# M507A.net
KiCad netlist of a schematic drawn in EAGLE
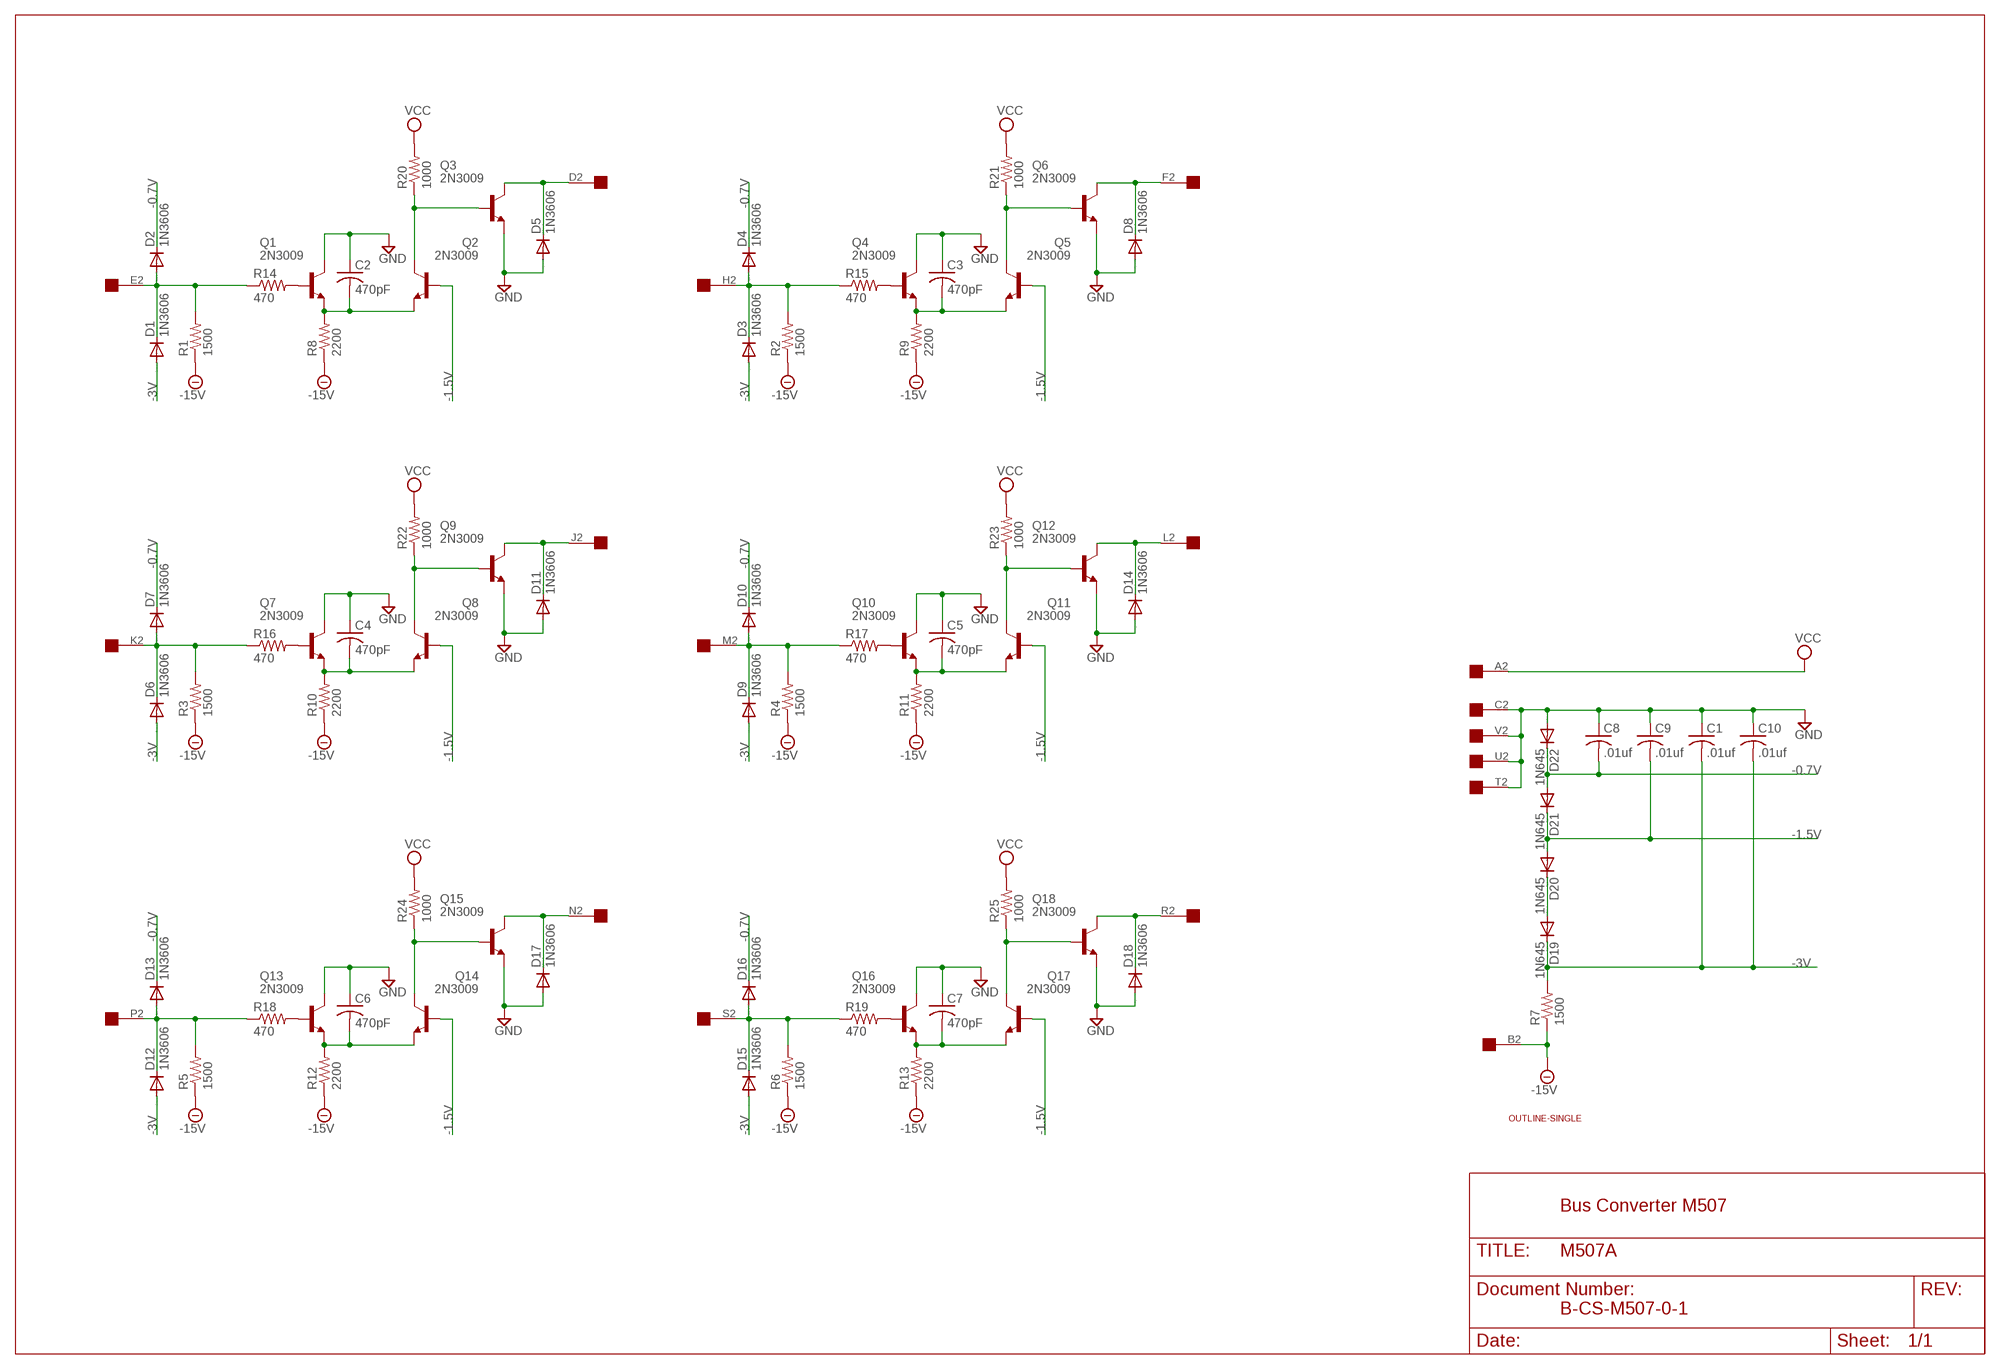
[diagram p0: schematic, sheet 1]

(export (version "E")
  (design (tool "Eeschema 10.0.6"))
  (components
    (comp (ref "C1")
      (value ".01uf")
      (footprint "eagle-import:C050-025X075")
      (libsource (lib "eagle-import") (part "C-US050-025X075"))
    )
    (comp (ref "C2")
      (value "470pF")
      (footprint "eagle-import:C050-025X075")
      (libsource (lib "eagle-import") (part "C-US050-025X075"))
    )
    (comp (ref "C3")
      (value "470pF")
      (footprint "eagle-import:C050-025X075")
      (libsource (lib "eagle-import") (part "C-US050-025X075"))
    )
    (comp (ref "C4")
      (value "470pF")
      (footprint "eagle-import:C050-025X075")
      (libsource (lib "eagle-import") (part "C-US050-025X075"))
    )
    (comp (ref "C5")
      (value "470pF")
      (footprint "eagle-import:C050-025X075")
      (libsource (lib "eagle-import") (part "C-US050-025X075"))
    )
    (comp (ref "C6")
      (value "470pF")
      (footprint "eagle-import:C050-025X075")
      (libsource (lib "eagle-import") (part "C-US050-025X075"))
    )
    (comp (ref "C7")
      (value "470pF")
      (footprint "eagle-import:C050-025X075")
      (libsource (lib "eagle-import") (part "C-US050-025X075"))
    )
    (comp (ref "C8")
      (value ".01uf")
      (footprint "eagle-import:C050-025X075")
      (libsource (lib "eagle-import") (part "C-US050-025X075"))
    )
    (comp (ref "C9")
      (value ".01uf")
      (footprint "eagle-import:C050-025X075")
      (libsource (lib "eagle-import") (part "C-US050-025X075"))
    )
    (comp (ref "C10")
      (value ".01uf")
      (footprint "eagle-import:C050-025X075")
      (libsource (lib "eagle-import") (part "C-US050-025X075"))
    )
    (comp (ref "D1")
      (value "1N3606")
      (footprint "eagle-import:DO35-10")
      (libsource (lib "eagle-import") (part "1N4148DO35-10"))
    )
    (comp (ref "D2")
      (value "1N3606")
      (footprint "eagle-import:DO35-10")
      (libsource (lib "eagle-import") (part "1N4148DO35-10"))
    )
    (comp (ref "D3")
      (value "1N3606")
      (footprint "eagle-import:DO35-10")
      (libsource (lib "eagle-import") (part "1N4148DO35-10"))
    )
    (comp (ref "D4")
      (value "1N3606")
      (footprint "eagle-import:DO35-10")
      (libsource (lib "eagle-import") (part "1N4148DO35-10"))
    )
    (comp (ref "D5")
      (value "1N3606")
      (footprint "eagle-import:DO35-10")
      (libsource (lib "eagle-import") (part "1N4148DO35-10"))
    )
    (comp (ref "D6")
      (value "1N3606")
      (footprint "eagle-import:DO35-10")
      (libsource (lib "eagle-import") (part "1N4148DO35-10"))
    )
    (comp (ref "D7")
      (value "1N3606")
      (footprint "eagle-import:DO35-10")
      (libsource (lib "eagle-import") (part "1N4148DO35-10"))
    )
    (comp (ref "D8")
      (value "1N3606")
      (footprint "eagle-import:DO35-10")
      (libsource (lib "eagle-import") (part "1N4148DO35-10"))
    )
    (comp (ref "D9")
      (value "1N3606")
      (footprint "eagle-import:DO35-10")
      (libsource (lib "eagle-import") (part "1N4148DO35-10"))
    )
    (comp (ref "D10")
      (value "1N3606")
      (footprint "eagle-import:DO35-10")
      (libsource (lib "eagle-import") (part "1N4148DO35-10"))
    )
    (comp (ref "D11")
      (value "1N3606")
      (footprint "eagle-import:DO35-10")
      (libsource (lib "eagle-import") (part "1N4148DO35-10"))
    )
    (comp (ref "D12")
      (value "1N3606")
      (footprint "eagle-import:DO35-10")
      (libsource (lib "eagle-import") (part "1N4148DO35-10"))
    )
    (comp (ref "D13")
      (value "1N3606")
      (footprint "eagle-import:DO35-10")
      (libsource (lib "eagle-import") (part "1N4148DO35-10"))
    )
    (comp (ref "D14")
      (value "1N3606")
      (footprint "eagle-import:DO35-10")
      (libsource (lib "eagle-import") (part "1N4148DO35-10"))
    )
    (comp (ref "D15")
      (value "1N3606")
      (footprint "eagle-import:DO35-10")
      (libsource (lib "eagle-import") (part "1N4148DO35-10"))
    )
    (comp (ref "D16")
      (value "1N3606")
      (footprint "eagle-import:DO35-10")
      (libsource (lib "eagle-import") (part "1N4148DO35-10"))
    )
    (comp (ref "D17")
      (value "1N3606")
      (footprint "eagle-import:DO35-10")
      (libsource (lib "eagle-import") (part "1N4148DO35-10"))
    )
    (comp (ref "D18")
      (value "1N3606")
      (footprint "eagle-import:DO35-10")
      (libsource (lib "eagle-import") (part "1N4148DO35-10"))
    )
    (comp (ref "D19")
      (value "1N645")
      (footprint "eagle-import:DO35-10")
      (libsource (lib "eagle-import") (part "1N4148DO35-10"))
    )
    (comp (ref "D20")
      (value "1N645")
      (footprint "eagle-import:DO35-10")
      (libsource (lib "eagle-import") (part "1N4148DO35-10"))
    )
    (comp (ref "D21")
      (value "1N645")
      (footprint "eagle-import:DO35-10")
      (libsource (lib "eagle-import") (part "1N4148DO35-10"))
    )
    (comp (ref "D22")
      (value "1N645")
      (footprint "eagle-import:DO35-10")
      (libsource (lib "eagle-import") (part "1N4148DO35-10"))
    )
    (comp (ref "Q1")
      (value "2N3009")
      (footprint "eagle-import:TO39")
      (libsource (lib "eagle-import") (part "2N3019"))
    )
    (comp (ref "Q2")
      (value "2N3009")
      (footprint "eagle-import:TO39")
      (libsource (lib "eagle-import") (part "2N3019"))
    )
    (comp (ref "Q3")
      (value "2N3009")
      (footprint "eagle-import:TO39")
      (libsource (lib "eagle-import") (part "2N3019"))
    )
    (comp (ref "Q4")
      (value "2N3009")
      (footprint "eagle-import:TO39")
      (libsource (lib "eagle-import") (part "2N3019"))
    )
    (comp (ref "Q5")
      (value "2N3009")
      (footprint "eagle-import:TO39")
      (libsource (lib "eagle-import") (part "2N3019"))
    )
    (comp (ref "Q6")
      (value "2N3009")
      (footprint "eagle-import:TO39")
      (libsource (lib "eagle-import") (part "2N3019"))
    )
    (comp (ref "Q7")
      (value "2N3009")
      (footprint "eagle-import:TO39")
      (libsource (lib "eagle-import") (part "2N3019"))
    )
    (comp (ref "Q8")
      (value "2N3009")
      (footprint "eagle-import:TO39")
      (libsource (lib "eagle-import") (part "2N3019"))
    )
    (comp (ref "Q9")
      (value "2N3009")
      (footprint "eagle-import:TO39")
      (libsource (lib "eagle-import") (part "2N3019"))
    )
    (comp (ref "Q10")
      (value "2N3009")
      (footprint "eagle-import:TO39")
      (libsource (lib "eagle-import") (part "2N3019"))
    )
    (comp (ref "Q11")
      (value "2N3009")
      (footprint "eagle-import:TO39")
      (libsource (lib "eagle-import") (part "2N3019"))
    )
    (comp (ref "Q12")
      (value "2N3009")
      (footprint "eagle-import:TO39")
      (libsource (lib "eagle-import") (part "2N3019"))
    )
    (comp (ref "Q13")
      (value "2N3009")
      (footprint "eagle-import:TO39")
      (libsource (lib "eagle-import") (part "2N3019"))
    )
    (comp (ref "Q14")
      (value "2N3009")
      (footprint "eagle-import:TO39")
      (libsource (lib "eagle-import") (part "2N3019"))
    )
    (comp (ref "Q15")
      (value "2N3009")
      (footprint "eagle-import:TO39")
      (libsource (lib "eagle-import") (part "2N3019"))
    )
    (comp (ref "Q16")
      (value "2N3009")
      (footprint "eagle-import:TO39")
      (libsource (lib "eagle-import") (part "2N3019"))
    )
    (comp (ref "Q17")
      (value "2N3009")
      (footprint "eagle-import:TO39")
      (libsource (lib "eagle-import") (part "2N3019"))
    )
    (comp (ref "Q18")
      (value "2N3009")
      (footprint "eagle-import:TO39")
      (libsource (lib "eagle-import") (part "2N3019"))
    )
    (comp (ref "R1")
      (value "1500")
      (footprint "eagle-import:0207_10")
      (libsource (lib "eagle-import") (part "R-US_0207/10"))
    )
    (comp (ref "R2")
      (value "1500")
      (footprint "eagle-import:0207_10")
      (libsource (lib "eagle-import") (part "R-US_0207/10"))
    )
    (comp (ref "R3")
      (value "1500")
      (footprint "eagle-import:0207_10")
      (libsource (lib "eagle-import") (part "R-US_0207/10"))
    )
    (comp (ref "R4")
      (value "1500")
      (footprint "eagle-import:0207_10")
      (libsource (lib "eagle-import") (part "R-US_0207/10"))
    )
    (comp (ref "R5")
      (value "1500")
      (footprint "eagle-import:0207_10")
      (libsource (lib "eagle-import") (part "R-US_0207/10"))
    )
    (comp (ref "R6")
      (value "1500")
      (footprint "eagle-import:0207_10")
      (libsource (lib "eagle-import") (part "R-US_0207/10"))
    )
    (comp (ref "R7")
      (value "1500")
      (footprint "eagle-import:0207_10")
      (libsource (lib "eagle-import") (part "R-US_0207/10"))
    )
    (comp (ref "R8")
      (value "2200")
      (footprint "eagle-import:0207_10")
      (libsource (lib "eagle-import") (part "R-US_0207/10"))
    )
    (comp (ref "R9")
      (value "2200")
      (footprint "eagle-import:0207_10")
      (libsource (lib "eagle-import") (part "R-US_0207/10"))
    )
    (comp (ref "R10")
      (value "2200")
      (footprint "eagle-import:0207_10")
      (libsource (lib "eagle-import") (part "R-US_0207/10"))
    )
    (comp (ref "R11")
      (value "2200")
      (footprint "eagle-import:0207_10")
      (libsource (lib "eagle-import") (part "R-US_0207/10"))
    )
    (comp (ref "R12")
      (value "2200")
      (footprint "eagle-import:0207_10")
      (libsource (lib "eagle-import") (part "R-US_0207/10"))
    )
    (comp (ref "R13")
      (value "2200")
      (footprint "eagle-import:0207_10")
      (libsource (lib "eagle-import") (part "R-US_0207/10"))
    )
    (comp (ref "R14")
      (value "470")
      (footprint "eagle-import:0207_10")
      (libsource (lib "eagle-import") (part "R-US_0207/10"))
    )
    (comp (ref "R15")
      (value "470")
      (footprint "eagle-import:0207_10")
      (libsource (lib "eagle-import") (part "R-US_0207/10"))
    )
    (comp (ref "R16")
      (value "470")
      (footprint "eagle-import:0207_10")
      (libsource (lib "eagle-import") (part "R-US_0207/10"))
    )
    (comp (ref "R17")
      (value "470")
      (footprint "eagle-import:0207_10")
      (libsource (lib "eagle-import") (part "R-US_0207/10"))
    )
    (comp (ref "R18")
      (value "470")
      (footprint "eagle-import:0207_10")
      (libsource (lib "eagle-import") (part "R-US_0207/10"))
    )
    (comp (ref "R19")
      (value "470")
      (footprint "eagle-import:0207_10")
      (libsource (lib "eagle-import") (part "R-US_0207/10"))
    )
    (comp (ref "R20")
      (value "1000")
      (footprint "eagle-import:0207_10")
      (libsource (lib "eagle-import") (part "R-US_0207/10"))
    )
    (comp (ref "R21")
      (value "1000")
      (footprint "eagle-import:0207_10")
      (libsource (lib "eagle-import") (part "R-US_0207/10"))
    )
    (comp (ref "R22")
      (value "1000")
      (footprint "eagle-import:0207_10")
      (libsource (lib "eagle-import") (part "R-US_0207/10"))
    )
    (comp (ref "R23")
      (value "1000")
      (footprint "eagle-import:0207_10")
      (libsource (lib "eagle-import") (part "R-US_0207/10"))
    )
    (comp (ref "R24")
      (value "1000")
      (footprint "eagle-import:0207_10")
      (libsource (lib "eagle-import") (part "R-US_0207/10"))
    )
    (comp (ref "R25")
      (value "1000")
      (footprint "eagle-import:0207_10")
      (libsource (lib "eagle-import") (part "R-US_0207/10"))
    )
    (comp (ref "U$3")
      (value "EDGE-1")
      (footprint "eagle-import:EDGE-CON1")
      (libsource (lib "eagle-import") (part "EDGE-1"))
    )
    (comp (ref "U$4")
      (value "OUTLINE-SINGLE")
      (footprint "eagle-import:SINGLE")
      (libsource (lib "eagle-import") (part "OUTLINE-SINGLE"))
    )
  )
  (nets
    (net (code "1") (name "-15V") (class "Default")
      (node (ref "R1") (pin "1") (pinfunction "1_1") (pintype "passive"))
      (node (ref "R10") (pin "1") (pinfunction "1_1") (pintype "passive"))
      (node (ref "R11") (pin "1") (pinfunction "1_1") (pintype "passive"))
      (node (ref "R12") (pin "1") (pinfunction "1_1") (pintype "passive"))
      (node (ref "R13") (pin "1") (pinfunction "1_1") (pintype "passive"))
      (node (ref "R2") (pin "1") (pinfunction "1_1") (pintype "passive"))
      (node (ref "R3") (pin "1") (pinfunction "1_1") (pintype "passive"))
      (node (ref "R4") (pin "1") (pinfunction "1_1") (pintype "passive"))
      (node (ref "R5") (pin "1") (pinfunction "1_1") (pintype "passive"))
      (node (ref "R6") (pin "1") (pinfunction "1_1") (pintype "passive"))
      (node (ref "R7") (pin "1") (pinfunction "1_1") (pintype "passive"))
      (node (ref "R8") (pin "1") (pinfunction "1_1") (pintype "passive"))
      (node (ref "R9") (pin "1") (pinfunction "1_1") (pintype "passive"))
      (node (ref "U$3") (pin "B2") (pinfunction "1_B2") (pintype "bidirectional"))
    )
    (net (code "2") (name "/-0.7V") (class "Default")
      (node (ref "C8") (pin "2") (pinfunction "2_2") (pintype "passive"))
      (node (ref "D10") (pin "C") (pinfunction "C_C") (pintype "passive"))
      (node (ref "D13") (pin "C") (pinfunction "C_C") (pintype "passive"))
      (node (ref "D16") (pin "C") (pinfunction "C_C") (pintype "passive"))
      (node (ref "D2") (pin "C") (pinfunction "C_C") (pintype "passive"))
      (node (ref "D21") (pin "A") (pinfunction "A_A") (pintype "passive"))
      (node (ref "D22") (pin "C") (pinfunction "C_C") (pintype "passive"))
      (node (ref "D4") (pin "C") (pinfunction "C_C") (pintype "passive"))
      (node (ref "D7") (pin "C") (pinfunction "C_C") (pintype "passive"))
    )
    (net (code "3") (name "/-1.5V") (class "Default")
      (node (ref "C9") (pin "2") (pinfunction "2_2") (pintype "passive"))
      (node (ref "D20") (pin "A") (pinfunction "A_A") (pintype "passive"))
      (node (ref "D21") (pin "C") (pinfunction "C_C") (pintype "passive"))
      (node (ref "Q11") (pin "2") (pinfunction "B_2") (pintype "passive"))
      (node (ref "Q14") (pin "2") (pinfunction "B_2") (pintype "passive"))
      (node (ref "Q17") (pin "2") (pinfunction "B_2") (pintype "passive"))
      (node (ref "Q2") (pin "2") (pinfunction "B_2") (pintype "passive"))
      (node (ref "Q5") (pin "2") (pinfunction "B_2") (pintype "passive"))
      (node (ref "Q8") (pin "2") (pinfunction "B_2") (pintype "passive"))
    )
    (net (code "4") (name "/-3V") (class "Default")
      (node (ref "C1") (pin "2") (pinfunction "2_2") (pintype "passive"))
      (node (ref "C10") (pin "2") (pinfunction "2_2") (pintype "passive"))
      (node (ref "D1") (pin "A") (pinfunction "A_A") (pintype "passive"))
      (node (ref "D12") (pin "A") (pinfunction "A_A") (pintype "passive"))
      (node (ref "D15") (pin "A") (pinfunction "A_A") (pintype "passive"))
      (node (ref "D19") (pin "C") (pinfunction "C_C") (pintype "passive"))
      (node (ref "D3") (pin "A") (pinfunction "A_A") (pintype "passive"))
      (node (ref "D6") (pin "A") (pinfunction "A_A") (pintype "passive"))
      (node (ref "D9") (pin "A") (pinfunction "A_A") (pintype "passive"))
      (node (ref "R7") (pin "2") (pinfunction "2_2") (pintype "passive"))
    )
    (net (code "5") (name "GND") (class "Default")
      (node (ref "C1") (pin "1") (pinfunction "1_1") (pintype "passive"))
      (node (ref "C10") (pin "1") (pinfunction "1_1") (pintype "passive"))
      (node (ref "C2") (pin "1") (pinfunction "1_1") (pintype "passive"))
      (node (ref "C3") (pin "1") (pinfunction "1_1") (pintype "passive"))
      (node (ref "C4") (pin "1") (pinfunction "1_1") (pintype "passive"))
      (node (ref "C5") (pin "1") (pinfunction "1_1") (pintype "passive"))
      (node (ref "C6") (pin "1") (pinfunction "1_1") (pintype "passive"))
      (node (ref "C7") (pin "1") (pinfunction "1_1") (pintype "passive"))
      (node (ref "C8") (pin "1") (pinfunction "1_1") (pintype "passive"))
      (node (ref "C9") (pin "1") (pinfunction "1_1") (pintype "passive"))
      (node (ref "D11") (pin "A") (pinfunction "A_A") (pintype "passive"))
      (node (ref "D14") (pin "A") (pinfunction "A_A") (pintype "passive"))
      (node (ref "D17") (pin "A") (pinfunction "A_A") (pintype "passive"))
      (node (ref "D18") (pin "A") (pinfunction "A_A") (pintype "passive"))
      (node (ref "D22") (pin "A") (pinfunction "A_A") (pintype "passive"))
      (node (ref "D5") (pin "A") (pinfunction "A_A") (pintype "passive"))
      (node (ref "D8") (pin "A") (pinfunction "A_A") (pintype "passive"))
      (node (ref "Q1") (pin "3") (pinfunction "C_3") (pintype "passive"))
      (node (ref "Q10") (pin "3") (pinfunction "C_3") (pintype "passive"))
      (node (ref "Q12") (pin "1") (pinfunction "E_1") (pintype "passive"))
      (node (ref "Q13") (pin "3") (pinfunction "C_3") (pintype "passive"))
      (node (ref "Q15") (pin "1") (pinfunction "E_1") (pintype "passive"))
      (node (ref "Q16") (pin "3") (pinfunction "C_3") (pintype "passive"))
      (node (ref "Q18") (pin "1") (pinfunction "E_1") (pintype "passive"))
      (node (ref "Q3") (pin "1") (pinfunction "E_1") (pintype "passive"))
      (node (ref "Q4") (pin "3") (pinfunction "C_3") (pintype "passive"))
      (node (ref "Q6") (pin "1") (pinfunction "E_1") (pintype "passive"))
      (node (ref "Q7") (pin "3") (pinfunction "C_3") (pintype "passive"))
      (node (ref "Q9") (pin "1") (pinfunction "E_1") (pintype "passive"))
      (node (ref "U$3") (pin "C2") (pinfunction "1_C2") (pintype "bidirectional"))
      (node (ref "U$3") (pin "T2") (pinfunction "1_T2") (pintype "bidirectional"))
      (node (ref "U$3") (pin "U2") (pinfunction "1_U2") (pintype "bidirectional"))
      (node (ref "U$3") (pin "V2") (pinfunction "1_V2") (pintype "bidirectional"))
    )
    (net (code "6") (name "Net-(D19-PadA)") (class "Default")
      (node (ref "D19") (pin "A") (pinfunction "A_A") (pintype "passive"))
      (node (ref "D20") (pin "C") (pinfunction "C_C") (pintype "passive"))
    )
    (net (code "7") (name "Net-(Q1-B)") (class "Default")
      (node (ref "Q1") (pin "2") (pinfunction "B_2") (pintype "passive"))
      (node (ref "R14") (pin "2") (pinfunction "2_2") (pintype "passive"))
    )
    (net (code "8") (name "Net-(Q1-E)") (class "Default")
      (node (ref "C2") (pin "2") (pinfunction "2_2") (pintype "passive"))
      (node (ref "Q1") (pin "1") (pinfunction "E_1") (pintype "passive"))
      (node (ref "Q2") (pin "1") (pinfunction "E_1") (pintype "passive"))
      (node (ref "R8") (pin "2") (pinfunction "2_2") (pintype "passive"))
    )
    (net (code "9") (name "Net-(Q2-C)") (class "Default")
      (node (ref "Q2") (pin "3") (pinfunction "C_3") (pintype "passive"))
      (node (ref "Q3") (pin "2") (pinfunction "B_2") (pintype "passive"))
      (node (ref "R20") (pin "1") (pinfunction "1_1") (pintype "passive"))
    )
    (net (code "10") (name "Net-(Q3-C)") (class "Default")
      (node (ref "D5") (pin "C") (pinfunction "C_C") (pintype "passive"))
      (node (ref "Q3") (pin "3") (pinfunction "C_3") (pintype "passive"))
      (node (ref "U$3") (pin "D2") (pinfunction "1_D2") (pintype "bidirectional"))
    )
    (net (code "11") (name "Net-(Q4-B)") (class "Default")
      (node (ref "Q4") (pin "2") (pinfunction "B_2") (pintype "passive"))
      (node (ref "R15") (pin "2") (pinfunction "2_2") (pintype "passive"))
    )
    (net (code "12") (name "Net-(Q4-E)") (class "Default")
      (node (ref "C3") (pin "2") (pinfunction "2_2") (pintype "passive"))
      (node (ref "Q4") (pin "1") (pinfunction "E_1") (pintype "passive"))
      (node (ref "Q5") (pin "1") (pinfunction "E_1") (pintype "passive"))
      (node (ref "R9") (pin "2") (pinfunction "2_2") (pintype "passive"))
    )
    (net (code "13") (name "Net-(Q5-C)") (class "Default")
      (node (ref "Q5") (pin "3") (pinfunction "C_3") (pintype "passive"))
      (node (ref "Q6") (pin "2") (pinfunction "B_2") (pintype "passive"))
      (node (ref "R21") (pin "1") (pinfunction "1_1") (pintype "passive"))
    )
    (net (code "14") (name "Net-(Q6-C)") (class "Default")
      (node (ref "D8") (pin "C") (pinfunction "C_C") (pintype "passive"))
      (node (ref "Q6") (pin "3") (pinfunction "C_3") (pintype "passive"))
      (node (ref "U$3") (pin "F2") (pinfunction "1_F2") (pintype "bidirectional"))
    )
    (net (code "15") (name "Net-(Q7-B)") (class "Default")
      (node (ref "Q7") (pin "2") (pinfunction "B_2") (pintype "passive"))
      (node (ref "R16") (pin "2") (pinfunction "2_2") (pintype "passive"))
    )
    (net (code "16") (name "Net-(Q7-E)") (class "Default")
      (node (ref "C4") (pin "2") (pinfunction "2_2") (pintype "passive"))
      (node (ref "Q7") (pin "1") (pinfunction "E_1") (pintype "passive"))
      (node (ref "Q8") (pin "1") (pinfunction "E_1") (pintype "passive"))
      (node (ref "R10") (pin "2") (pinfunction "2_2") (pintype "passive"))
    )
    (net (code "17") (name "Net-(Q8-C)") (class "Default")
      (node (ref "Q8") (pin "3") (pinfunction "C_3") (pintype "passive"))
      (node (ref "Q9") (pin "2") (pinfunction "B_2") (pintype "passive"))
      (node (ref "R22") (pin "1") (pinfunction "1_1") (pintype "passive"))
    )
    (net (code "18") (name "Net-(Q9-C)") (class "Default")
      (node (ref "D11") (pin "C") (pinfunction "C_C") (pintype "passive"))
      (node (ref "Q9") (pin "3") (pinfunction "C_3") (pintype "passive"))
      (node (ref "U$3") (pin "J2") (pinfunction "1_J2") (pintype "bidirectional"))
    )
    (net (code "19") (name "Net-(Q10-B)") (class "Default")
      (node (ref "Q10") (pin "2") (pinfunction "B_2") (pintype "passive"))
      (node (ref "R17") (pin "2") (pinfunction "2_2") (pintype "passive"))
    )
    (net (code "20") (name "Net-(Q10-E)") (class "Default")
      (node (ref "C5") (pin "2") (pinfunction "2_2") (pintype "passive"))
      (node (ref "Q10") (pin "1") (pinfunction "E_1") (pintype "passive"))
      (node (ref "Q11") (pin "1") (pinfunction "E_1") (pintype "passive"))
      (node (ref "R11") (pin "2") (pinfunction "2_2") (pintype "passive"))
    )
    (net (code "21") (name "Net-(Q11-C)") (class "Default")
      (node (ref "Q11") (pin "3") (pinfunction "C_3") (pintype "passive"))
      (node (ref "Q12") (pin "2") (pinfunction "B_2") (pintype "passive"))
      (node (ref "R23") (pin "1") (pinfunction "1_1") (pintype "passive"))
    )
    (net (code "22") (name "Net-(Q12-C)") (class "Default")
      (node (ref "D14") (pin "C") (pinfunction "C_C") (pintype "passive"))
      (node (ref "Q12") (pin "3") (pinfunction "C_3") (pintype "passive"))
      (node (ref "U$3") (pin "L2") (pinfunction "1_L2") (pintype "bidirectional"))
    )
    (net (code "23") (name "Net-(Q13-B)") (class "Default")
      (node (ref "Q13") (pin "2") (pinfunction "B_2") (pintype "passive"))
      (node (ref "R18") (pin "2") (pinfunction "2_2") (pintype "passive"))
    )
    (net (code "24") (name "Net-(Q13-E)") (class "Default")
      (node (ref "C6") (pin "2") (pinfunction "2_2") (pintype "passive"))
      (node (ref "Q13") (pin "1") (pinfunction "E_1") (pintype "passive"))
      (node (ref "Q14") (pin "1") (pinfunction "E_1") (pintype "passive"))
      (node (ref "R12") (pin "2") (pinfunction "2_2") (pintype "passive"))
    )
    (net (code "25") (name "Net-(Q14-C)") (class "Default")
      (node (ref "Q14") (pin "3") (pinfunction "C_3") (pintype "passive"))
      (node (ref "Q15") (pin "2") (pinfunction "B_2") (pintype "passive"))
      (node (ref "R24") (pin "1") (pinfunction "1_1") (pintype "passive"))
    )
    (net (code "26") (name "Net-(Q15-C)") (class "Default")
      (node (ref "D17") (pin "C") (pinfunction "C_C") (pintype "passive"))
      (node (ref "Q15") (pin "3") (pinfunction "C_3") (pintype "passive"))
      (node (ref "U$3") (pin "N2") (pinfunction "1_N2") (pintype "bidirectional"))
    )
    (net (code "27") (name "Net-(Q16-B)") (class "Default")
      (node (ref "Q16") (pin "2") (pinfunction "B_2") (pintype "passive"))
      (node (ref "R19") (pin "2") (pinfunction "2_2") (pintype "passive"))
    )
    (net (code "28") (name "Net-(Q16-E)") (class "Default")
      (node (ref "C7") (pin "2") (pinfunction "2_2") (pintype "passive"))
      (node (ref "Q16") (pin "1") (pinfunction "E_1") (pintype "passive"))
      (node (ref "Q17") (pin "1") (pinfunction "E_1") (pintype "passive"))
      (node (ref "R13") (pin "2") (pinfunction "2_2") (pintype "passive"))
    )
    (net (code "29") (name "Net-(Q17-C)") (class "Default")
      (node (ref "Q17") (pin "3") (pinfunction "C_3") (pintype "passive"))
      (node (ref "Q18") (pin "2") (pinfunction "B_2") (pintype "passive"))
      (node (ref "R25") (pin "1") (pinfunction "1_1") (pintype "passive"))
    )
    (net (code "30") (name "Net-(Q18-C)") (class "Default")
      (node (ref "D18") (pin "C") (pinfunction "C_C") (pintype "passive"))
      (node (ref "Q18") (pin "3") (pinfunction "C_3") (pintype "passive"))
      (node (ref "U$3") (pin "R2") (pinfunction "1_R2") (pintype "bidirectional"))
    )
    (net (code "31") (name "Net-(U$3E-1)") (class "Default")
      (node (ref "D1") (pin "C") (pinfunction "C_C") (pintype "passive"))
      (node (ref "D2") (pin "A") (pinfunction "A_A") (pintype "passive"))
      (node (ref "R1") (pin "2") (pinfunction "2_2") (pintype "passive"))
      (node (ref "R14") (pin "1") (pinfunction "1_1") (pintype "passive"))
      (node (ref "U$3") (pin "E2") (pinfunction "1_E2") (pintype "bidirectional"))
    )
    (net (code "32") (name "Net-(U$3G-1)") (class "Default")
      (node (ref "D3") (pin "C") (pinfunction "C_C") (pintype "passive"))
      (node (ref "D4") (pin "A") (pinfunction "A_A") (pintype "passive"))
      (node (ref "R15") (pin "1") (pinfunction "1_1") (pintype "passive"))
      (node (ref "R2") (pin "2") (pinfunction "2_2") (pintype "passive"))
      (node (ref "U$3") (pin "H2") (pinfunction "1_H2") (pintype "bidirectional"))
    )
    (net (code "33") (name "Net-(U$3I-1)") (class "Default")
      (node (ref "D6") (pin "C") (pinfunction "C_C") (pintype "passive"))
      (node (ref "D7") (pin "A") (pinfunction "A_A") (pintype "passive"))
      (node (ref "R16") (pin "1") (pinfunction "1_1") (pintype "passive"))
      (node (ref "R3") (pin "2") (pinfunction "2_2") (pintype "passive"))
      (node (ref "U$3") (pin "K2") (pinfunction "1_K2") (pintype "bidirectional"))
    )
    (net (code "34") (name "Net-(U$3K-1)") (class "Default")
      (node (ref "D10") (pin "A") (pinfunction "A_A") (pintype "passive"))
      (node (ref "D9") (pin "C") (pinfunction "C_C") (pintype "passive"))
      (node (ref "R17") (pin "1") (pinfunction "1_1") (pintype "passive"))
      (node (ref "R4") (pin "2") (pinfunction "2_2") (pintype "passive"))
      (node (ref "U$3") (pin "M2") (pinfunction "1_M2") (pintype "bidirectional"))
    )
    (net (code "35") (name "Net-(U$3M-1)") (class "Default")
      (node (ref "D12") (pin "C") (pinfunction "C_C") (pintype "passive"))
      (node (ref "D13") (pin "A") (pinfunction "A_A") (pintype "passive"))
      (node (ref "R18") (pin "1") (pinfunction "1_1") (pintype "passive"))
      (node (ref "R5") (pin "2") (pinfunction "2_2") (pintype "passive"))
      (node (ref "U$3") (pin "P2") (pinfunction "1_P2") (pintype "bidirectional"))
    )
    (net (code "36") (name "Net-(U$3O-1)") (class "Default")
      (node (ref "D15") (pin "C") (pinfunction "C_C") (pintype "passive"))
      (node (ref "D16") (pin "A") (pinfunction "A_A") (pintype "passive"))
      (node (ref "R19") (pin "1") (pinfunction "1_1") (pintype "passive"))
      (node (ref "R6") (pin "2") (pinfunction "2_2") (pintype "passive"))
      (node (ref "U$3") (pin "S2") (pinfunction "1_S2") (pintype "bidirectional"))
    )
    (net (code "37") (name "VCC") (class "Default")
      (node (ref "R20") (pin "2") (pinfunction "2_2") (pintype "passive"))
      (node (ref "R21") (pin "2") (pinfunction "2_2") (pintype "passive"))
      (node (ref "R22") (pin "2") (pinfunction "2_2") (pintype "passive"))
      (node (ref "R23") (pin "2") (pinfunction "2_2") (pintype "passive"))
      (node (ref "R24") (pin "2") (pinfunction "2_2") (pintype "passive"))
      (node (ref "R25") (pin "2") (pinfunction "2_2") (pintype "passive"))
      (node (ref "U$3") (pin "A2") (pinfunction "1_A2") (pintype "bidirectional"))
    )
  )
)
